# Fiber_interlock.net
KiCad netlist of a schematic drawn in Altium Designer
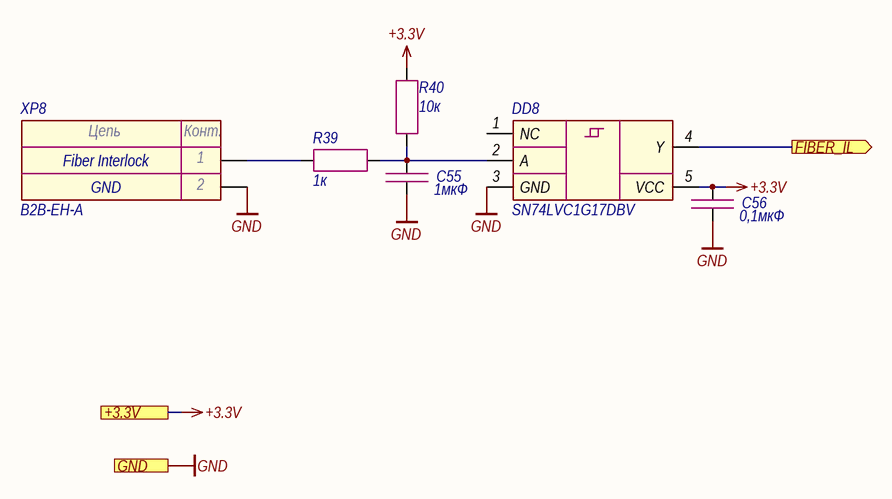
[diagram p0: Fiber_interlock.SchDoc]

(export (version "E")
  (design (tool "Eeschema 10.0.6"))
  (components
    (comp (ref "C55")
      (value "1мкФ")
      (footprint "Pcb_library:CAP_0603")
      (fields (field (name "MANUFACTURER") "Murata"))
      (libsource (lib "Schem_library") (part "Capacitor"))
    )
    (comp (ref "C56")
      (value "0,1мкФ")
      (footprint "Pcb_library:CAP_0603")
      (fields (field (name "MANUFACTURER") "Murata"))
      (libsource (lib "Schem_library") (part "Capacitor"))
    )
    (comp (ref "DD8")
      (value "SN74LVC1G17DBV")
      (footprint "Pcb_library:SOT-23-5")
      (fields (field (name "MANUFACTURER") "Texas Instruments"))
      (libsource (lib "Schem_library") (part "SN74LVC1G17"))
    )
    (comp (ref "R39")
      (value "1к")
      (footprint "Pcb_library:RES_0603")
      (fields (field (name "MANUFACTURER") "Yageo"))
      (libsource (lib "Schem_library") (part "Resistor"))
    )
    (comp (ref "R40")
      (value "10к")
      (footprint "Pcb_library:RES_0603")
      (fields (field (name "MANUFACTURER") "Yageo"))
      (libsource (lib "Schem_library") (part "Resistor"))
    )
    (comp (ref "XP8")
      (value "B2B-EH-A")
      (footprint "Pcb_library:B2B-EH-A")
      (fields (field (name "MANUFACTURER") "JST"))
      (libsource (lib "Schem_library") (part "Connector-2"))
    )
  )
  (nets
    (net (code "1") (name "+3.3V") (class "Default")
      (node (ref "C56") (pin "1") (pinfunction "1_1") (pintype "passive"))
      (node (ref "DD8") (pin "5") (pinfunction "VCC_5") (pintype "passive"))
      (node (ref "R40") (pin "2") (pinfunction "2_2") (pintype "passive"))
    )
    (net (code "2") (name "/FIBER_IL") (class "Default")
      (node (ref "DD8") (pin "4") (pinfunction "Y_4") (pintype "passive"))
    )
    (net (code "3") (name "GND") (class "Default")
      (node (ref "C55") (pin "2") (pinfunction "2_2") (pintype "passive"))
      (node (ref "C56") (pin "2") (pinfunction "2_2") (pintype "passive"))
      (node (ref "DD8") (pin "3") (pinfunction "GND_3") (pintype "passive"))
      (node (ref "XP8") (pin "2") (pintype "passive"))
    )
    (net (code "4") (name "Net-(DD8-A)") (class "Default")
      (node (ref "C55") (pin "1") (pinfunction "1_1") (pintype "passive"))
      (node (ref "DD8") (pin "2") (pinfunction "A_2") (pintype "passive"))
      (node (ref "R39") (pin "2") (pinfunction "2_2") (pintype "passive"))
      (node (ref "R40") (pin "1") (pinfunction "1_1") (pintype "passive"))
    )
    (net (code "5") (name "Net-(R39-Pad1)") (class "Default")
      (node (ref "R39") (pin "1") (pinfunction "1_1") (pintype "passive"))
      (node (ref "XP8") (pin "1") (pintype "passive"))
    )
    (net (code "6") (name "unconnected-(DD8-NC-Pad1)") (class "Default")
      (node (ref "DD8") (pin "1") (pinfunction "NC_1") (pintype "passive"))
    )
  )
)
